# 08_DDR2.net
KiCad netlist of a schematic drawn in Altium Designer
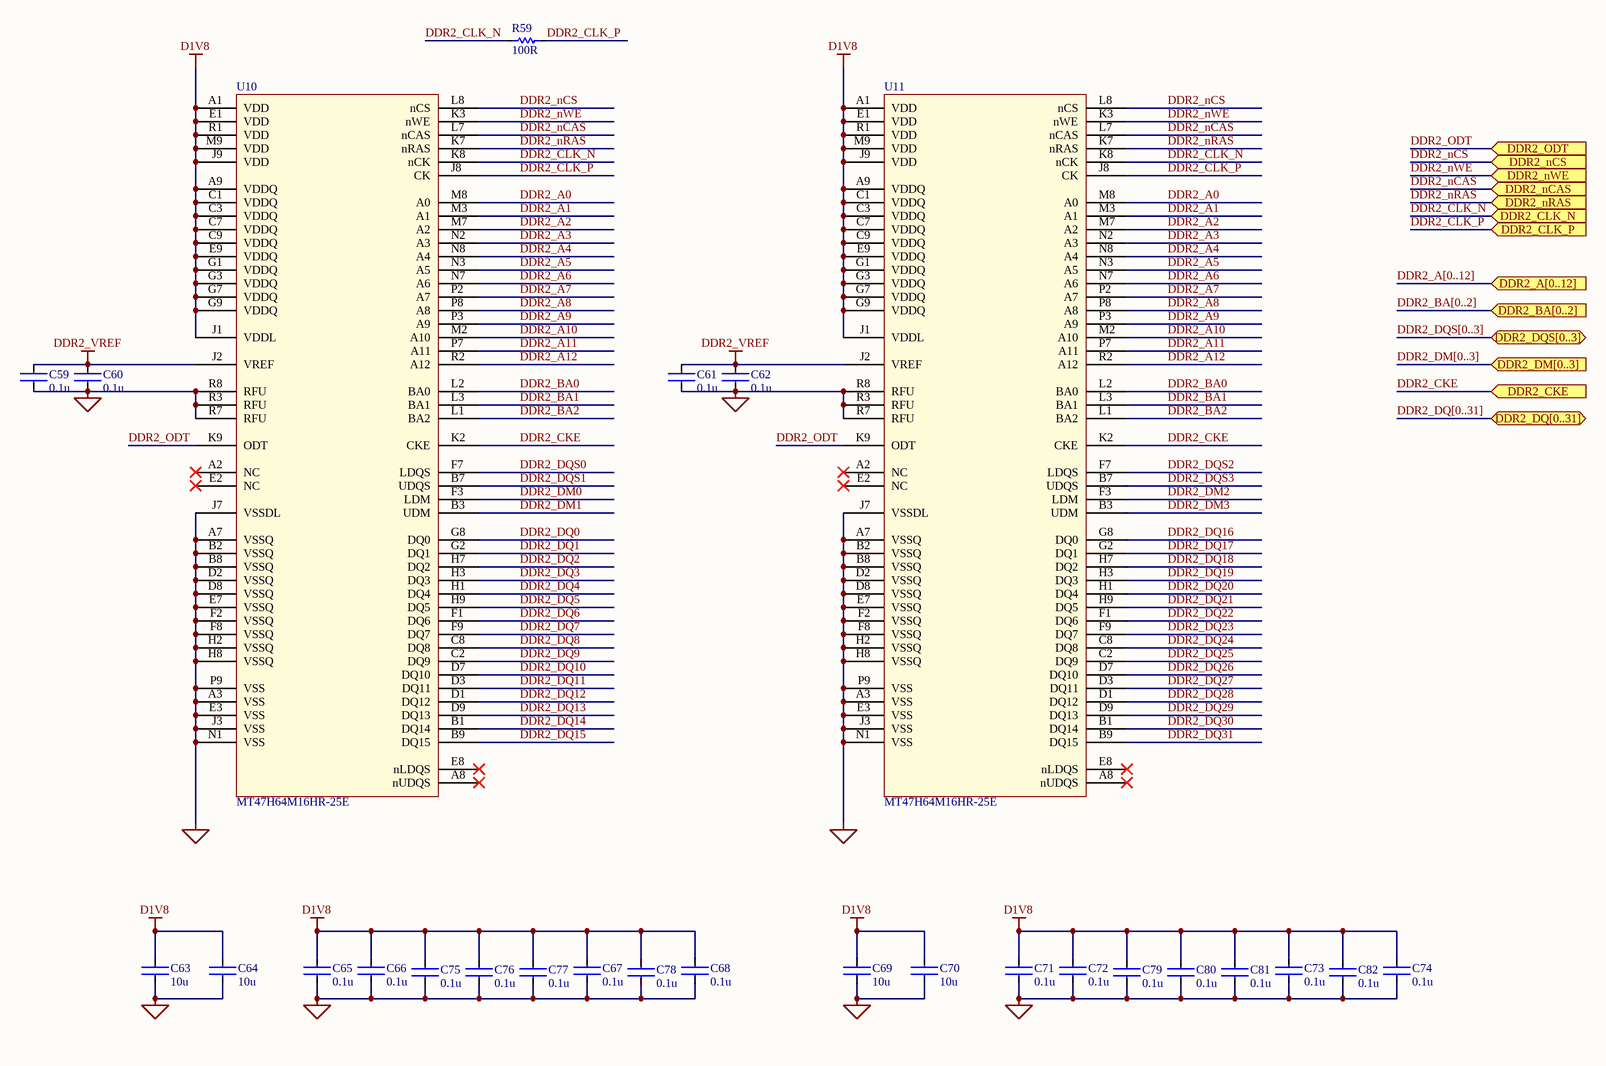
[diagram p0: 08_DDR2.SchDoc]

(export (version "E")
  (design (tool "Eeschema 10.0.6"))
  (components
    (comp (ref "C59")
      (value "0.1u")
      (footprint "C0402")
      (description "CAP,Ceramic,X7R,10%,16V,0.1uF,0402")
      (libsource (lib "C0402") (part "CAP011"))
    )
    (comp (ref "C60")
      (value "0.1u")
      (footprint "C0402")
      (description "CAP,Ceramic,X7R,10%,16V,0.1uF,0402")
      (libsource (lib "C0402") (part "CAP011"))
    )
    (comp (ref "C61")
      (value "0.1u")
      (footprint "C0402")
      (description "CAP,Ceramic,X7R,10%,16V,0.1uF,0402")
      (libsource (lib "C0402") (part "CAP011"))
    )
    (comp (ref "C62")
      (value "0.1u")
      (footprint "C0402")
      (description "CAP,Ceramic,X7R,10%,16V,0.1uF,0402")
      (libsource (lib "C0402") (part "CAP011"))
    )
    (comp (ref "C63")
      (value "10u")
      (footprint "CAPC1608X09N_C0603")
      (description "CAP,Ceramic,X7R,10%,6.3V,10uF,0603")
      (libsource (lib "C0603") (part "CAP113"))
    )
    (comp (ref "C64")
      (value "10u")
      (footprint "CAPC1608X09N_C0603")
      (description "CAP,Ceramic,X7R,10%,6.3V,10uF,0603")
      (libsource (lib "C0603") (part "CAP113"))
    )
    (comp (ref "C65")
      (value "0.1u")
      (footprint "C0402")
      (description "CAP,Ceramic,X7R,10%,16V,0.1uF,0402")
      (libsource (lib "C0402") (part "CAP011"))
    )
    (comp (ref "C66")
      (value "0.1u")
      (footprint "C0402")
      (description "CAP,Ceramic,X7R,10%,16V,0.1uF,0402")
      (libsource (lib "C0402") (part "CAP011"))
    )
    (comp (ref "C67")
      (value "0.1u")
      (footprint "C0402")
      (description "CAP,Ceramic,X7R,10%,16V,0.1uF,0402")
      (libsource (lib "C0402") (part "CAP011"))
    )
    (comp (ref "C68")
      (value "0.1u")
      (footprint "C0402")
      (description "CAP,Ceramic,X7R,10%,16V,0.1uF,0402")
      (libsource (lib "C0402") (part "CAP011"))
    )
    (comp (ref "C69")
      (value "10u")
      (footprint "CAPC1608X09N_C0603")
      (description "CAP,Ceramic,X7R,10%,6.3V,10uF,0603")
      (libsource (lib "C0603") (part "CAP113"))
    )
    (comp (ref "C70")
      (value "10u")
      (footprint "CAPC1608X09N_C0603")
      (description "CAP,Ceramic,X7R,10%,6.3V,10uF,0603")
      (libsource (lib "C0603") (part "CAP113"))
    )
    (comp (ref "C71")
      (value "0.1u")
      (footprint "C0402")
      (description "CAP,Ceramic,X7R,10%,16V,0.1uF,0402")
      (libsource (lib "C0402") (part "CAP011"))
    )
    (comp (ref "C72")
      (value "0.1u")
      (footprint "C0402")
      (description "CAP,Ceramic,X7R,10%,16V,0.1uF,0402")
      (libsource (lib "C0402") (part "CAP011"))
    )
    (comp (ref "C73")
      (value "0.1u")
      (footprint "C0402")
      (description "CAP,Ceramic,X7R,10%,16V,0.1uF,0402")
      (libsource (lib "C0402") (part "CAP011"))
    )
    (comp (ref "C74")
      (value "0.1u")
      (footprint "C0402")
      (description "CAP,Ceramic,X7R,10%,16V,0.1uF,0402")
      (libsource (lib "C0402") (part "CAP011"))
    )
    (comp (ref "C75")
      (value "0.1u")
      (footprint "C0402")
      (description "CAP,Ceramic,X7R,10%,16V,0.1uF,0402")
      (libsource (lib "C0402") (part "CAP011"))
    )
    (comp (ref "C76")
      (value "0.1u")
      (footprint "C0402")
      (description "CAP,Ceramic,X7R,10%,16V,0.1uF,0402")
      (libsource (lib "C0402") (part "CAP011"))
    )
    (comp (ref "C77")
      (value "0.1u")
      (footprint "C0402")
      (description "CAP,Ceramic,X7R,10%,16V,0.1uF,0402")
      (libsource (lib "C0402") (part "CAP011"))
    )
    (comp (ref "C78")
      (value "0.1u")
      (footprint "C0402")
      (description "CAP,Ceramic,X7R,10%,16V,0.1uF,0402")
      (libsource (lib "C0402") (part "CAP011"))
    )
    (comp (ref "C79")
      (value "0.1u")
      (footprint "C0402")
      (description "CAP,Ceramic,X7R,10%,16V,0.1uF,0402")
      (libsource (lib "C0402") (part "CAP011"))
    )
    (comp (ref "C80")
      (value "0.1u")
      (footprint "C0402")
      (description "CAP,Ceramic,X7R,10%,16V,0.1uF,0402")
      (libsource (lib "C0402") (part "CAP011"))
    )
    (comp (ref "C81")
      (value "0.1u")
      (footprint "C0402")
      (description "CAP,Ceramic,X7R,10%,16V,0.1uF,0402")
      (libsource (lib "C0402") (part "CAP011"))
    )
    (comp (ref "C82")
      (value "0.1u")
      (footprint "C0402")
      (description "CAP,Ceramic,X7R,10%,16V,0.1uF,0402")
      (libsource (lib "C0402") (part "CAP011"))
    )
    (comp (ref "R59")
      (value "100R")
      (footprint "R0402")
      (description "RES,100R,1%,1/16W,0402")
      (libsource (lib "R0402") (part "RES019"))
    )
    (comp (ref "U10")
      (value "MT47H64M16HR-25E")
      (footprint "FBGA84_MT47H64M16HR-25E")
      (description "IC,DDR2 SDRAM,64Mx16,FBGA84")
      (libsource (lib "Micron") (part "MT47H64M16HR-25E"))
    )
    (comp (ref "U11")
      (value "MT47H64M16HR-25E")
      (footprint "FBGA84_MT47H64M16HR-25E")
      (description "IC,DDR2 SDRAM,64Mx16,FBGA84")
      (libsource (lib "Micron") (part "MT47H64M16HR-25E"))
    )
  )
  (nets
    (net (code "1") (name "/DDR2_A0") (class "Default")
      (node (ref "U10") (pin "M8") (pinfunction "A0_M8") (pintype "passive"))
      (node (ref "U11") (pin "M8") (pinfunction "A0_M8") (pintype "passive"))
    )
    (net (code "2") (name "/DDR2_A1") (class "Default")
      (node (ref "U10") (pin "M3") (pinfunction "A1_M3") (pintype "passive"))
      (node (ref "U11") (pin "M3") (pinfunction "A1_M3") (pintype "passive"))
    )
    (net (code "3") (name "/DDR2_A2") (class "Default")
      (node (ref "U10") (pin "M7") (pinfunction "A2_M7") (pintype "passive"))
      (node (ref "U11") (pin "M7") (pinfunction "A2_M7") (pintype "passive"))
    )
    (net (code "4") (name "/DDR2_A3") (class "Default")
      (node (ref "U10") (pin "N2") (pinfunction "A3_N2") (pintype "passive"))
      (node (ref "U11") (pin "N2") (pinfunction "A3_N2") (pintype "passive"))
    )
    (net (code "5") (name "/DDR2_A4") (class "Default")
      (node (ref "U10") (pin "N8") (pinfunction "A4_N8") (pintype "passive"))
      (node (ref "U11") (pin "N8") (pinfunction "A4_N8") (pintype "passive"))
    )
    (net (code "6") (name "/DDR2_A5") (class "Default")
      (node (ref "U10") (pin "N3") (pinfunction "A5_N3") (pintype "passive"))
      (node (ref "U11") (pin "N3") (pinfunction "A5_N3") (pintype "passive"))
    )
    (net (code "7") (name "/DDR2_A6") (class "Default")
      (node (ref "U10") (pin "N7") (pinfunction "A6_N7") (pintype "passive"))
      (node (ref "U11") (pin "N7") (pinfunction "A6_N7") (pintype "passive"))
    )
    (net (code "8") (name "/DDR2_A7") (class "Default")
      (node (ref "U10") (pin "P2") (pinfunction "A7_P2") (pintype "passive"))
      (node (ref "U11") (pin "P2") (pinfunction "A7_P2") (pintype "passive"))
    )
    (net (code "9") (name "/DDR2_A8") (class "Default")
      (node (ref "U10") (pin "P8") (pinfunction "A8_P8") (pintype "passive"))
      (node (ref "U11") (pin "P8") (pinfunction "A8_P8") (pintype "passive"))
    )
    (net (code "10") (name "/DDR2_A9") (class "Default")
      (node (ref "U10") (pin "P3") (pinfunction "A9_P3") (pintype "passive"))
      (node (ref "U11") (pin "P3") (pinfunction "A9_P3") (pintype "passive"))
    )
    (net (code "11") (name "/DDR2_A10") (class "Default")
      (node (ref "U10") (pin "M2") (pinfunction "A10_M2") (pintype "passive"))
      (node (ref "U11") (pin "M2") (pinfunction "A10_M2") (pintype "passive"))
    )
    (net (code "12") (name "/DDR2_A11") (class "Default")
      (node (ref "U10") (pin "P7") (pinfunction "A11_P7") (pintype "passive"))
      (node (ref "U11") (pin "P7") (pinfunction "A11_P7") (pintype "passive"))
    )
    (net (code "13") (name "/DDR2_A12") (class "Default")
      (node (ref "U10") (pin "R2") (pinfunction "A12_R2") (pintype "passive"))
      (node (ref "U11") (pin "R2") (pinfunction "A12_R2") (pintype "passive"))
    )
    (net (code "15") (name "/DDR2_BA0") (class "Default")
      (node (ref "U10") (pin "L2") (pinfunction "BA0_L2") (pintype "passive"))
      (node (ref "U11") (pin "L2") (pinfunction "BA0_L2") (pintype "passive"))
    )
    (net (code "16") (name "/DDR2_BA1") (class "Default")
      (node (ref "U10") (pin "L3") (pinfunction "BA1_L3") (pintype "passive"))
      (node (ref "U11") (pin "L3") (pinfunction "BA1_L3") (pintype "passive"))
    )
    (net (code "17") (name "/DDR2_BA2") (class "Default")
      (node (ref "U10") (pin "L1") (pinfunction "BA2_L1") (pintype "passive"))
      (node (ref "U11") (pin "L1") (pinfunction "BA2_L1") (pintype "passive"))
    )
    (net (code "19") (name "/DDR2_CKE") (class "Default")
      (node (ref "U10") (pin "K2") (pinfunction "CKE_K2") (pintype "passive"))
      (node (ref "U11") (pin "K2") (pinfunction "CKE_K2") (pintype "passive"))
    )
    (net (code "20") (name "/DDR2_CLK_N") (class "Default")
      (node (ref "R59") (pin "1") (pinfunction "0_1") (pintype "passive"))
      (node (ref "U10") (pin "K8") (pinfunction "nCK_K8") (pintype "passive"))
      (node (ref "U11") (pin "K8") (pinfunction "nCK_K8") (pintype "passive"))
    )
    (net (code "21") (name "/DDR2_CLK_P") (class "Default")
      (node (ref "R59") (pin "2") (pinfunction "2_2") (pintype "passive"))
      (node (ref "U10") (pin "J8") (pinfunction "CK_J8") (pintype "passive"))
      (node (ref "U11") (pin "J8") (pinfunction "CK_J8") (pintype "passive"))
    )
    (net (code "22") (name "/DDR2_DM0") (class "Default")
      (node (ref "U10") (pin "F3") (pinfunction "LDM_F3") (pintype "passive"))
    )
    (net (code "23") (name "/DDR2_DM1") (class "Default")
      (node (ref "U10") (pin "B3") (pinfunction "UDM_B3") (pintype "passive"))
    )
    (net (code "24") (name "/DDR2_DM2") (class "Default")
      (node (ref "U11") (pin "F3") (pinfunction "LDM_F3") (pintype "passive"))
    )
    (net (code "25") (name "/DDR2_DM3") (class "Default")
      (node (ref "U11") (pin "B3") (pinfunction "UDM_B3") (pintype "passive"))
    )
    (net (code "27") (name "/DDR2_DQ0") (class "Default")
      (node (ref "U10") (pin "G8") (pinfunction "DQ0_G8") (pintype "passive"))
    )
    (net (code "28") (name "/DDR2_DQ1") (class "Default")
      (node (ref "U10") (pin "G2") (pinfunction "DQ1_G2") (pintype "passive"))
    )
    (net (code "29") (name "/DDR2_DQ2") (class "Default")
      (node (ref "U10") (pin "H7") (pinfunction "DQ2_H7") (pintype "passive"))
    )
    (net (code "30") (name "/DDR2_DQ3") (class "Default")
      (node (ref "U10") (pin "H3") (pinfunction "DQ3_H3") (pintype "passive"))
    )
    (net (code "31") (name "/DDR2_DQ4") (class "Default")
      (node (ref "U10") (pin "H1") (pinfunction "DQ4_H1") (pintype "passive"))
    )
    (net (code "32") (name "/DDR2_DQ5") (class "Default")
      (node (ref "U10") (pin "H9") (pinfunction "DQ5_H9") (pintype "passive"))
    )
    (net (code "33") (name "/DDR2_DQ6") (class "Default")
      (node (ref "U10") (pin "F1") (pinfunction "DQ6_F1") (pintype "passive"))
    )
    (net (code "34") (name "/DDR2_DQ7") (class "Default")
      (node (ref "U10") (pin "F9") (pinfunction "DQ7_F9") (pintype "passive"))
    )
    (net (code "35") (name "/DDR2_DQ8") (class "Default")
      (node (ref "U10") (pin "C8") (pinfunction "DQ8_C8") (pintype "passive"))
    )
    (net (code "36") (name "/DDR2_DQ9") (class "Default")
      (node (ref "U10") (pin "C2") (pinfunction "DQ9_C2") (pintype "passive"))
    )
    (net (code "37") (name "/DDR2_DQ10") (class "Default")
      (node (ref "U10") (pin "D7") (pinfunction "DQ10_D7") (pintype "passive"))
    )
    (net (code "38") (name "/DDR2_DQ11") (class "Default")
      (node (ref "U10") (pin "D3") (pinfunction "DQ11_D3") (pintype "passive"))
    )
    (net (code "39") (name "/DDR2_DQ12") (class "Default")
      (node (ref "U10") (pin "D1") (pinfunction "DQ12_D1") (pintype "passive"))
    )
    (net (code "40") (name "/DDR2_DQ13") (class "Default")
      (node (ref "U10") (pin "D9") (pinfunction "DQ13_D9") (pintype "passive"))
    )
    (net (code "41") (name "/DDR2_DQ14") (class "Default")
      (node (ref "U10") (pin "B1") (pinfunction "DQ14_B1") (pintype "passive"))
    )
    (net (code "42") (name "/DDR2_DQ15") (class "Default")
      (node (ref "U10") (pin "B9") (pinfunction "DQ15_B9") (pintype "passive"))
    )
    (net (code "43") (name "/DDR2_DQ16") (class "Default")
      (node (ref "U11") (pin "G8") (pinfunction "DQ0_G8") (pintype "passive"))
    )
    (net (code "44") (name "/DDR2_DQ17") (class "Default")
      (node (ref "U11") (pin "G2") (pinfunction "DQ1_G2") (pintype "passive"))
    )
    (net (code "45") (name "/DDR2_DQ18") (class "Default")
      (node (ref "U11") (pin "H7") (pinfunction "DQ2_H7") (pintype "passive"))
    )
    (net (code "46") (name "/DDR2_DQ19") (class "Default")
      (node (ref "U11") (pin "H3") (pinfunction "DQ3_H3") (pintype "passive"))
    )
    (net (code "47") (name "/DDR2_DQ20") (class "Default")
      (node (ref "U11") (pin "H1") (pinfunction "DQ4_H1") (pintype "passive"))
    )
    (net (code "48") (name "/DDR2_DQ21") (class "Default")
      (node (ref "U11") (pin "H9") (pinfunction "DQ5_H9") (pintype "passive"))
    )
    (net (code "49") (name "/DDR2_DQ22") (class "Default")
      (node (ref "U11") (pin "F1") (pinfunction "DQ6_F1") (pintype "passive"))
    )
    (net (code "50") (name "/DDR2_DQ23") (class "Default")
      (node (ref "U11") (pin "F9") (pinfunction "DQ7_F9") (pintype "passive"))
    )
    (net (code "51") (name "/DDR2_DQ24") (class "Default")
      (node (ref "U11") (pin "C8") (pinfunction "DQ8_C8") (pintype "passive"))
    )
    (net (code "52") (name "/DDR2_DQ25") (class "Default")
      (node (ref "U11") (pin "C2") (pinfunction "DQ9_C2") (pintype "passive"))
    )
    (net (code "53") (name "/DDR2_DQ26") (class "Default")
      (node (ref "U11") (pin "D7") (pinfunction "DQ10_D7") (pintype "passive"))
    )
    (net (code "54") (name "/DDR2_DQ27") (class "Default")
      (node (ref "U11") (pin "D3") (pinfunction "DQ11_D3") (pintype "passive"))
    )
    (net (code "55") (name "/DDR2_DQ28") (class "Default")
      (node (ref "U11") (pin "D1") (pinfunction "DQ12_D1") (pintype "passive"))
    )
    (net (code "56") (name "/DDR2_DQ29") (class "Default")
      (node (ref "U11") (pin "D9") (pinfunction "DQ13_D9") (pintype "passive"))
    )
    (net (code "57") (name "/DDR2_DQ30") (class "Default")
      (node (ref "U11") (pin "B1") (pinfunction "DQ14_B1") (pintype "passive"))
    )
    (net (code "58") (name "/DDR2_DQ31") (class "Default")
      (node (ref "U11") (pin "B9") (pinfunction "DQ15_B9") (pintype "passive"))
    )
    (net (code "59") (name "/DDR2_DQS0") (class "Default")
      (node (ref "U10") (pin "F7") (pinfunction "LDQS_F7") (pintype "passive"))
    )
    (net (code "60") (name "/DDR2_DQS1") (class "Default")
      (node (ref "U10") (pin "B7") (pinfunction "UDQS_B7") (pintype "passive"))
    )
    (net (code "61") (name "/DDR2_DQS2") (class "Default")
      (node (ref "U11") (pin "F7") (pinfunction "LDQS_F7") (pintype "passive"))
    )
    (net (code "62") (name "/DDR2_DQS3") (class "Default")
      (node (ref "U11") (pin "B7") (pinfunction "UDQS_B7") (pintype "passive"))
    )
    (net (code "65") (name "/DDR2_ODT") (class "Default")
      (node (ref "U10") (pin "K9") (pinfunction "ODT_K9") (pintype "passive"))
      (node (ref "U11") (pin "K9") (pinfunction "ODT_K9") (pintype "passive"))
    )
    (net (code "66") (name "/DDR2_nCAS") (class "Default")
      (node (ref "U10") (pin "L7") (pinfunction "nCAS_L7") (pintype "passive"))
      (node (ref "U11") (pin "L7") (pinfunction "nCAS_L7") (pintype "passive"))
    )
    (net (code "67") (name "/DDR2_nCS") (class "Default")
      (node (ref "U10") (pin "L8") (pinfunction "nCS_L8") (pintype "passive"))
      (node (ref "U11") (pin "L8") (pinfunction "nCS_L8") (pintype "passive"))
    )
    (net (code "68") (name "/DDR2_nRAS") (class "Default")
      (node (ref "U10") (pin "K7") (pinfunction "nRAS_K7") (pintype "passive"))
      (node (ref "U11") (pin "K7") (pinfunction "nRAS_K7") (pintype "passive"))
    )
    (net (code "69") (name "/DDR2_nWE") (class "Default")
      (node (ref "U10") (pin "K3") (pinfunction "nWE_K3") (pintype "passive"))
      (node (ref "U11") (pin "K3") (pinfunction "nWE_K3") (pintype "passive"))
    )
    (net (code "70") (name "D1V8") (class "Default")
      (node (ref "C63") (pin "1") (pinfunction "0_1") (pintype "passive"))
      (node (ref "C64") (pin "1") (pinfunction "0_1") (pintype "passive"))
      (node (ref "C65") (pin "1") (pinfunction "0_1") (pintype "passive"))
      (node (ref "C66") (pin "1") (pinfunction "0_1") (pintype "passive"))
      (node (ref "C67") (pin "1") (pinfunction "0_1") (pintype "passive"))
      (node (ref "C68") (pin "1") (pinfunction "0_1") (pintype "passive"))
      (node (ref "C69") (pin "1") (pinfunction "0_1") (pintype "passive"))
      (node (ref "C70") (pin "1") (pinfunction "0_1") (pintype "passive"))
      (node (ref "C71") (pin "1") (pinfunction "0_1") (pintype "passive"))
      (node (ref "C72") (pin "1") (pinfunction "0_1") (pintype "passive"))
      (node (ref "C73") (pin "1") (pinfunction "0_1") (pintype "passive"))
      (node (ref "C74") (pin "1") (pinfunction "0_1") (pintype "passive"))
      (node (ref "C75") (pin "1") (pinfunction "0_1") (pintype "passive"))
      (node (ref "C76") (pin "1") (pinfunction "0_1") (pintype "passive"))
      (node (ref "C77") (pin "1") (pinfunction "0_1") (pintype "passive"))
      (node (ref "C78") (pin "1") (pinfunction "0_1") (pintype "passive"))
      (node (ref "C79") (pin "1") (pinfunction "0_1") (pintype "passive"))
      (node (ref "C80") (pin "1") (pinfunction "0_1") (pintype "passive"))
      (node (ref "C81") (pin "1") (pinfunction "0_1") (pintype "passive"))
      (node (ref "C82") (pin "1") (pinfunction "0_1") (pintype "passive"))
      (node (ref "U10") (pin "A1") (pinfunction "VDD_A1") (pintype "passive"))
      (node (ref "U10") (pin "A9") (pinfunction "VDDQ_A9") (pintype "passive"))
      (node (ref "U10") (pin "C1") (pinfunction "VDDQ_C1") (pintype "passive"))
      (node (ref "U10") (pin "C3") (pinfunction "VDDQ_C3") (pintype "passive"))
      (node (ref "U10") (pin "C7") (pinfunction "VDDQ_C7") (pintype "passive"))
      (node (ref "U10") (pin "C9") (pinfunction "VDDQ_C9") (pintype "passive"))
      (node (ref "U10") (pin "E1") (pinfunction "VDD_E1") (pintype "passive"))
      (node (ref "U10") (pin "E9") (pinfunction "VDDQ_E9") (pintype "passive"))
      (node (ref "U10") (pin "G1") (pinfunction "VDDQ_G1") (pintype "passive"))
      (node (ref "U10") (pin "G3") (pinfunction "VDDQ_G3") (pintype "passive"))
      (node (ref "U10") (pin "G7") (pinfunction "VDDQ_G7") (pintype "passive"))
      (node (ref "U10") (pin "G9") (pinfunction "VDDQ_G9") (pintype "passive"))
      (node (ref "U10") (pin "J1") (pinfunction "VDDL_J1") (pintype "passive"))
      (node (ref "U10") (pin "J9") (pinfunction "VDD_J9") (pintype "passive"))
      (node (ref "U10") (pin "M9") (pinfunction "VDD_M9") (pintype "passive"))
      (node (ref "U10") (pin "R1") (pinfunction "VDD_R1") (pintype "passive"))
      (node (ref "U11") (pin "A1") (pinfunction "VDD_A1") (pintype "passive"))
      (node (ref "U11") (pin "A9") (pinfunction "VDDQ_A9") (pintype "passive"))
      (node (ref "U11") (pin "C1") (pinfunction "VDDQ_C1") (pintype "passive"))
      (node (ref "U11") (pin "C3") (pinfunction "VDDQ_C3") (pintype "passive"))
      (node (ref "U11") (pin "C7") (pinfunction "VDDQ_C7") (pintype "passive"))
      (node (ref "U11") (pin "C9") (pinfunction "VDDQ_C9") (pintype "passive"))
      (node (ref "U11") (pin "E1") (pinfunction "VDD_E1") (pintype "passive"))
      (node (ref "U11") (pin "E9") (pinfunction "VDDQ_E9") (pintype "passive"))
      (node (ref "U11") (pin "G1") (pinfunction "VDDQ_G1") (pintype "passive"))
      (node (ref "U11") (pin "G3") (pinfunction "VDDQ_G3") (pintype "passive"))
      (node (ref "U11") (pin "G7") (pinfunction "VDDQ_G7") (pintype "passive"))
      (node (ref "U11") (pin "G9") (pinfunction "VDDQ_G9") (pintype "passive"))
      (node (ref "U11") (pin "J1") (pinfunction "VDDL_J1") (pintype "passive"))
      (node (ref "U11") (pin "J9") (pinfunction "VDD_J9") (pintype "passive"))
      (node (ref "U11") (pin "M9") (pinfunction "VDD_M9") (pintype "passive"))
      (node (ref "U11") (pin "R1") (pinfunction "VDD_R1") (pintype "passive"))
    )
    (net (code "71") (name "DDR2_VREF") (class "Default")
      (node (ref "C59") (pin "1") (pinfunction "0_1") (pintype "passive"))
      (node (ref "C60") (pin "1") (pinfunction "0_1") (pintype "passive"))
      (node (ref "C61") (pin "1") (pinfunction "0_1") (pintype "passive"))
      (node (ref "C62") (pin "1") (pinfunction "0_1") (pintype "passive"))
      (node (ref "U10") (pin "J2") (pinfunction "VREF_J2") (pintype "passive"))
      (node (ref "U11") (pin "J2") (pinfunction "VREF_J2") (pintype "passive"))
    )
    (net (code "72") (name "GND") (class "Default")
      (node (ref "C59") (pin "2") (pinfunction "1_2") (pintype "passive"))
      (node (ref "C61") (pin "2") (pinfunction "1_2") (pintype "passive"))
      (node (ref "C62") (pin "2") (pinfunction "1_2") (pintype "passive"))
      (node (ref "C63") (pin "2") (pinfunction "1_2") (pintype "passive"))
      (node (ref "C64") (pin "2") (pinfunction "1_2") (pintype "passive"))
      (node (ref "C65") (pin "2") (pinfunction "1_2") (pintype "passive"))
      (node (ref "C66") (pin "2") (pinfunction "1_2") (pintype "passive"))
      (node (ref "C67") (pin "2") (pinfunction "1_2") (pintype "passive"))
      (node (ref "C68") (pin "2") (pinfunction "1_2") (pintype "passive"))
      (node (ref "C69") (pin "2") (pinfunction "1_2") (pintype "passive"))
      (node (ref "C70") (pin "2") (pinfunction "1_2") (pintype "passive"))
      (node (ref "C71") (pin "2") (pinfunction "1_2") (pintype "passive"))
      (node (ref "C72") (pin "2") (pinfunction "1_2") (pintype "passive"))
      (node (ref "C73") (pin "2") (pinfunction "1_2") (pintype "passive"))
      (node (ref "C74") (pin "2") (pinfunction "1_2") (pintype "passive"))
      (node (ref "C75") (pin "2") (pinfunction "1_2") (pintype "passive"))
      (node (ref "C76") (pin "2") (pinfunction "1_2") (pintype "passive"))
      (node (ref "C77") (pin "2") (pinfunction "1_2") (pintype "passive"))
      (node (ref "C78") (pin "2") (pinfunction "1_2") (pintype "passive"))
      (node (ref "C79") (pin "2") (pinfunction "1_2") (pintype "passive"))
      (node (ref "C80") (pin "2") (pinfunction "1_2") (pintype "passive"))
      (node (ref "C81") (pin "2") (pinfunction "1_2") (pintype "passive"))
      (node (ref "C82") (pin "2") (pinfunction "1_2") (pintype "passive"))
      (node (ref "U10") (pin "A3") (pinfunction "VSS_A3") (pintype "passive"))
      (node (ref "U10") (pin "A7") (pinfunction "VSSQ_A7") (pintype "passive"))
      (node (ref "U10") (pin "B2") (pinfunction "VSSQ_B2") (pintype "passive"))
      (node (ref "U10") (pin "B8") (pinfunction "VSSQ_B8") (pintype "passive"))
      (node (ref "U10") (pin "D2") (pinfunction "VSSQ_D2") (pintype "passive"))
      (node (ref "U10") (pin "D8") (pinfunction "VSSQ_D8") (pintype "passive"))
      (node (ref "U10") (pin "E3") (pinfunction "VSS_E3") (pintype "passive"))
      (node (ref "U10") (pin "E7") (pinfunction "VSSQ_E7") (pintype "passive"))
      (node (ref "U10") (pin "F2") (pinfunction "VSSQ_F2") (pintype "passive"))
      (node (ref "U10") (pin "F8") (pinfunction "VSSQ_F8") (pintype "passive"))
      (node (ref "U10") (pin "H2") (pinfunction "VSSQ_H2") (pintype "passive"))
      (node (ref "U10") (pin "H8") (pinfunction "VSSQ_H8") (pintype "passive"))
      (node (ref "U10") (pin "J3") (pinfunction "VSS_J3") (pintype "passive"))
      (node (ref "U10") (pin "J7") (pinfunction "VSSDL_J7") (pintype "passive"))
      (node (ref "U10") (pin "N1") (pinfunction "VSS_N1") (pintype "passive"))
      (node (ref "U10") (pin "P9") (pinfunction "VSS_P9") (pintype "passive"))
      (node (ref "U10") (pin "R3") (pinfunction "RFU_R3") (pintype "passive"))
      (node (ref "U10") (pin "R7") (pinfunction "RFU_R7") (pintype "passive"))
      (node (ref "U10") (pin "R8") (pinfunction "RFU_R8") (pintype "passive"))
      (node (ref "U11") (pin "A3") (pinfunction "VSS_A3") (pintype "passive"))
      (node (ref "U11") (pin "A7") (pinfunction "VSSQ_A7") (pintype "passive"))
      (node (ref "U11") (pin "B2") (pinfunction "VSSQ_B2") (pintype "passive"))
      (node (ref "U11") (pin "B8") (pinfunction "VSSQ_B8") (pintype "passive"))
      (node (ref "U11") (pin "D2") (pinfunction "VSSQ_D2") (pintype "passive"))
      (node (ref "U11") (pin "D8") (pinfunction "VSSQ_D8") (pintype "passive"))
      (node (ref "U11") (pin "E3") (pinfunction "VSS_E3") (pintype "passive"))
      (node (ref "U11") (pin "E7") (pinfunction "VSSQ_E7") (pintype "passive"))
      (node (ref "U11") (pin "F2") (pinfunction "VSSQ_F2") (pintype "passive"))
      (node (ref "U11") (pin "F8") (pinfunction "VSSQ_F8") (pintype "passive"))
      (node (ref "U11") (pin "H2") (pinfunction "VSSQ_H2") (pintype "passive"))
      (node (ref "U11") (pin "H8") (pinfunction "VSSQ_H8") (pintype "passive"))
      (node (ref "U11") (pin "J3") (pinfunction "VSS_J3") (pintype "passive"))
      (node (ref "U11") (pin "J7") (pinfunction "VSSDL_J7") (pintype "passive"))
      (node (ref "U11") (pin "N1") (pinfunction "VSS_N1") (pintype "passive"))
      (node (ref "U11") (pin "P9") (pinfunction "VSS_P9") (pintype "passive"))
      (node (ref "U11") (pin "R3") (pinfunction "RFU_R3") (pintype "passive"))
      (node (ref "U11") (pin "R7") (pinfunction "RFU_R7") (pintype "passive"))
      (node (ref "U11") (pin "R8") (pinfunction "RFU_R8") (pintype "passive"))
    )
    (net (code "73") (name "unconnected-(C60-1-Pad2)") (class "Default")
      (node (ref "C60") (pin "2") (pinfunction "1_2") (pintype "passive"))
    )
    (net (code "74") (name "unconnected-(U10-NC-PadA2)") (class "Default")
      (node (ref "U10") (pin "A2") (pinfunction "NC_A2") (pintype "passive+no_connect"))
    )
    (net (code "75") (name "unconnected-(U10-NC-PadE2)") (class "Default")
      (node (ref "U10") (pin "E2") (pinfunction "NC_E2") (pintype "passive+no_connect"))
    )
    (net (code "76") (name "unconnected-(U10-nLDQS-PadE8)") (class "Default")
      (node (ref "U10") (pin "E8") (pinfunction "nLDQS_E8") (pintype "passive+no_connect"))
    )
    (net (code "77") (name "unconnected-(U10-nUDQS-PadA8)") (class "Default")
      (node (ref "U10") (pin "A8") (pinfunction "nUDQS_A8") (pintype "passive+no_connect"))
    )
    (net (code "78") (name "unconnected-(U11-NC-PadA2)") (class "Default")
      (node (ref "U11") (pin "A2") (pinfunction "NC_A2") (pintype "passive+no_connect"))
    )
    (net (code "79") (name "unconnected-(U11-NC-PadE2)") (class "Default")
      (node (ref "U11") (pin "E2") (pinfunction "NC_E2") (pintype "passive+no_connect"))
    )
    (net (code "80") (name "unconnected-(U11-nLDQS-PadE8)") (class "Default")
      (node (ref "U11") (pin "E8") (pinfunction "nLDQS_E8") (pintype "passive+no_connect"))
    )
    (net (code "81") (name "unconnected-(U11-nUDQS-PadA8)") (class "Default")
      (node (ref "U11") (pin "A8") (pinfunction "nUDQS_A8") (pintype "passive+no_connect"))
    )
  )
)
